# meteo_station_main.net
KiCad netlist of a schematic drawn in EasyEDA Pro
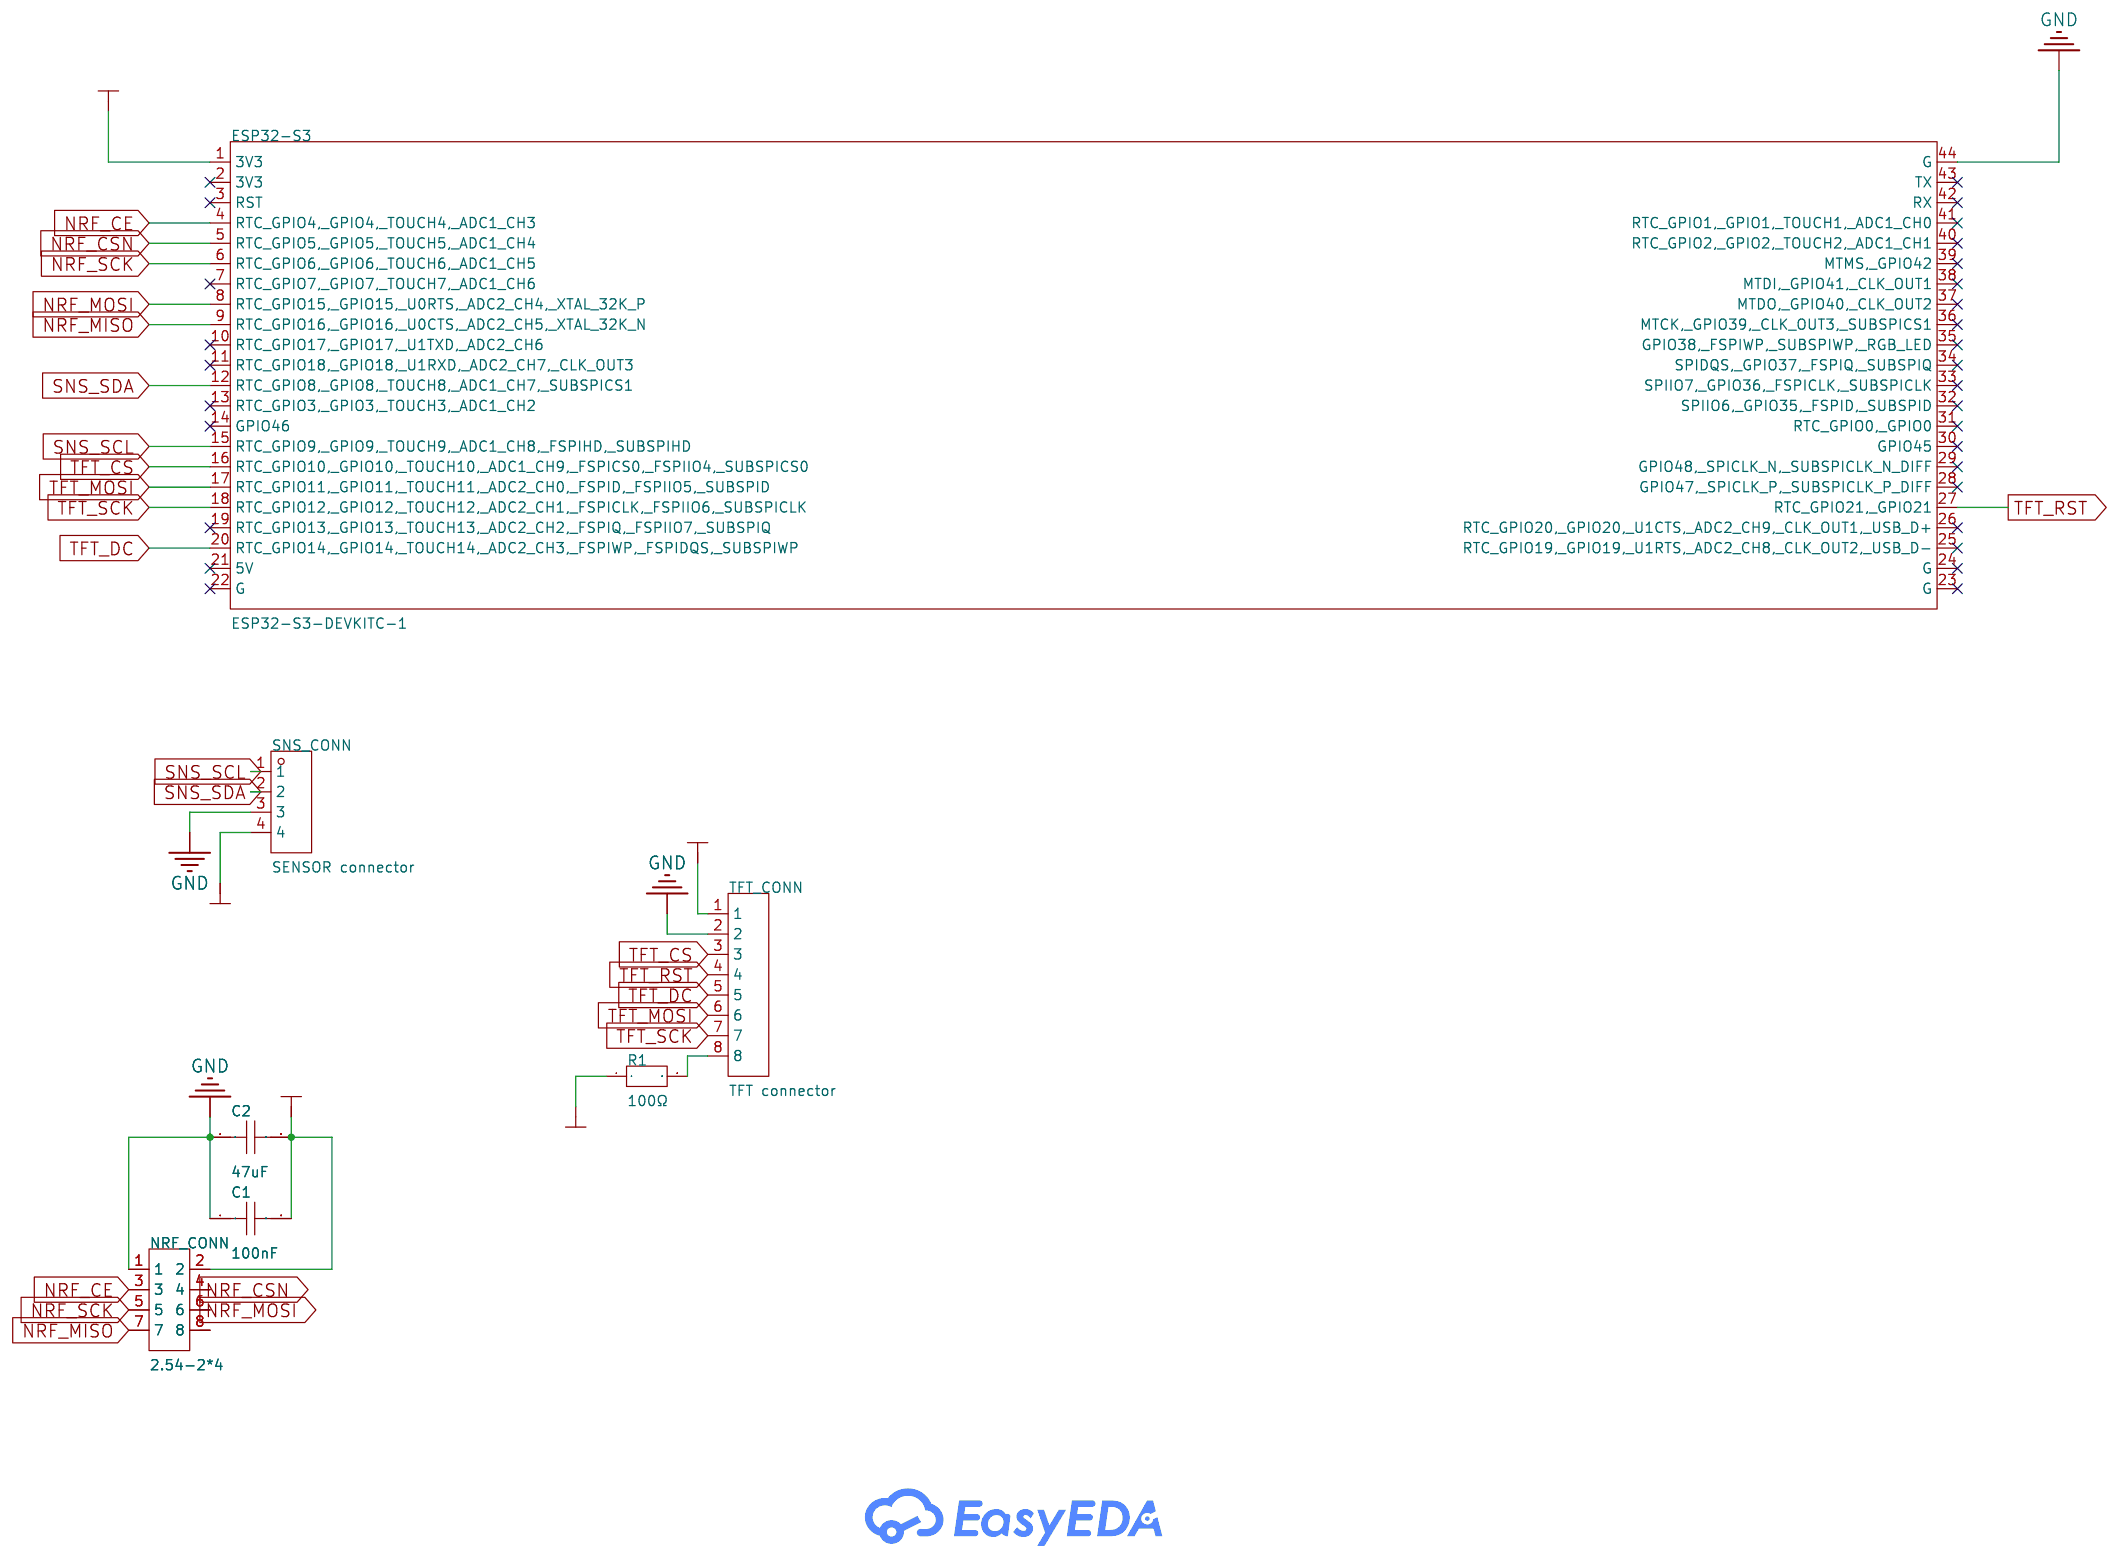
[diagram p0: schematic sheet]

(export (version "E")
  (design (tool "Eeschema 10.0.6"))
  (components
    (comp (ref "C1")
      (value "100nF")
      (footprint "easyedapro:CAP-TH_L5.5-W2.4-P5.08-D0.6")
      (fields
        (field (name "Manufacturer Part") "CC1H104ZC1ED3F5O1100")
        (field (name "Manufacturer") "Dersonic(德尔创)")
      )
      (libsource (lib "easyedapro") (part "CC1H104ZC1ED3F5O1100"))
    )
    (comp (ref "C2")
      (value "47uF")
      (footprint "easyedapro:CAP-TH_L5.5-W2.4-P5.08-D0.6")
      (fields
        (field (name "Manufacturer Part") "CC1H104ZC1ED3F5O1100")
        (field (name "Manufacturer") "Dersonic(德尔创)")
      )
      (libsource (lib "easyedapro") (part "CC1H104ZC1ED3F5O1100"))
    )
    (comp (ref "ESP32-S3")
      (value "ESP32-S3-DEVKITC-1")
      (footprint "easyedapro:CONN-TH_ESP32-S3-DEVKITC-1U-N8")
      (fields (field (name "Manufacturer") "ESPRESSIF(乐鑫)"))
      (libsource (lib "easyedapro") (part "ESP32-S3-DEVKITC-1-N8"))
    )
    (comp (ref "NRF_CONN")
      (value "2.54-2*4")
      (footprint "easyedapro:HDR-TH_8P-P2.54-V-F-R2-C4-S2.54")
      (fields (field (name "Manufacturer") "ZHOURI(洲日)"))
      (libsource (lib "easyedapro") (part "2.54-2*4"))
    )
    (comp (ref "R1")
      (value "100Ω")
      (footprint "easyedapro:RES-TH_BD5.6-L14.0-P18.00-D0.8")
      (description "Resistance: Tolerance:±1% Tolerance:±1%")
      (fields (field (name "Manufacturer Part") "RLP03100R0FB15") (field (name "Manufacturer") "VISHAY(威世)"))
      (libsource (lib "easyedapro") (part "RLP03100R0FB15"))
    )
    (comp (ref "SNS_CONN")
      (value "SENSOR connector")
      (footprint "easyedapro:HDR-TH_4P-P2.54-V-M-3")
      (libsource (lib "easyedapro") (part "SIP4-CON4排针"))
    )
    (comp (ref "TFT_CONN")
      (value "TFT connector")
      (footprint "easyedapro:CONN-TH_8P-P2.54_XH2.54_C9900012080")
      (libsource (lib "easyedapro") (part "XH2.54-8PIN"))
    )
  )
  (nets
    (net (code "1") (name "GND") (class "Default")
      (node (ref "C1") (pin "1") (pinfunction "1_1") (pintype "unspecified"))
      (node (ref "C2") (pin "1") (pinfunction "1_1") (pintype "unspecified"))
      (node (ref "ESP32-S3") (pin "44") (pinfunction "G_44") (pintype "unspecified"))
      (node (ref "NRF_CONN") (pin "1") (pinfunction "1_1") (pintype "unspecified"))
      (node (ref "SNS_CONN") (pin "3") (pinfunction "3_3") (pintype "unspecified"))
      (node (ref "TFT_CONN") (pin "2") (pinfunction "2_2") (pintype "unspecified"))
    )
    (net (code "2") (name "NRF_CE") (class "Default")
      (node (ref "ESP32-S3") (pin "4") (pinfunction "RTC_GPIO4,_GPIO4,_TOUCH4,_ADC1_CH3_4") (pintype "unspecified"))
      (node (ref "NRF_CONN") (pin "3") (pinfunction "3_3") (pintype "unspecified"))
    )
    (net (code "3") (name "NRF_CSN") (class "Default")
      (node (ref "ESP32-S3") (pin "5") (pinfunction "RTC_GPIO5,_GPIO5,_TOUCH5,_ADC1_CH4_5") (pintype "unspecified"))
      (node (ref "NRF_CONN") (pin "4") (pinfunction "4_4") (pintype "unspecified"))
    )
    (net (code "4") (name "NRF_MISO") (class "Default")
      (node (ref "ESP32-S3") (pin "9") (pinfunction "RTC_GPIO16,_GPIO16,_U0CTS,_ADC2_CH5,_XTAL_32K_N_9") (pintype "unspecified"))
      (node (ref "NRF_CONN") (pin "7") (pinfunction "7_7") (pintype "unspecified"))
    )
    (net (code "5") (name "NRF_MOSI") (class "Default")
      (node (ref "ESP32-S3") (pin "8") (pinfunction "RTC_GPIO15,_GPIO15,_U0RTS,_ADC2_CH4,_XTAL_32K_P_8") (pintype "unspecified"))
      (node (ref "NRF_CONN") (pin "6") (pinfunction "6_6") (pintype "unspecified"))
    )
    (net (code "6") (name "NRF_SCK") (class "Default")
      (node (ref "ESP32-S3") (pin "6") (pinfunction "RTC_GPIO6,_GPIO6,_TOUCH6,_ADC1_CH5_6") (pintype "unspecified"))
      (node (ref "NRF_CONN") (pin "5") (pinfunction "5_5") (pintype "unspecified"))
    )
    (net (code "7") (name "Net-(R1-Pad2)") (class "Default")
      (node (ref "R1") (pin "2") (pinfunction "2_2") (pintype "unspecified"))
      (node (ref "TFT_CONN") (pin "8") (pinfunction "8_8") (pintype "unspecified"))
    )
    (net (code "8") (name "SNS_SCL") (class "Default")
      (node (ref "ESP32-S3") (pin "15") (pinfunction "RTC_GPIO9,_GPIO9,_TOUCH9,_ADC1_CH8,_FSPIHD,_SUBSPIHD_15") (pintype "unspecified"))
      (node (ref "SNS_CONN") (pin "1") (pinfunction "1_1") (pintype "unspecified"))
    )
    (net (code "9") (name "SNS_SDA") (class "Default")
      (node (ref "ESP32-S3") (pin "12") (pinfunction "RTC_GPIO8,_GPIO8,_TOUCH8,_ADC1_CH7,_SUBSPICS1_12") (pintype "unspecified"))
      (node (ref "SNS_CONN") (pin "2") (pinfunction "2_2") (pintype "unspecified"))
    )
    (net (code "10") (name "TFT_CS") (class "Default")
      (node (ref "ESP32-S3") (pin "16") (pinfunction "RTC_GPIO10,_GPIO10,_TOUCH10,_ADC1_CH9,_FSPICS0,_FSPIIO4,_SUBSPICS0_16") (pintype "unspecified"))
      (node (ref "TFT_CONN") (pin "3") (pinfunction "3_3") (pintype "unspecified"))
    )
    (net (code "11") (name "TFT_DC") (class "Default")
      (node (ref "ESP32-S3") (pin "20") (pinfunction "RTC_GPIO14,_GPIO14,_TOUCH14,_ADC2_CH3,_FSPIWP,_FSPIDQS,_SUBSPIWP_20") (pintype "unspecified"))
      (node (ref "TFT_CONN") (pin "5") (pinfunction "5_5") (pintype "unspecified"))
    )
    (net (code "12") (name "TFT_MOSI") (class "Default")
      (node (ref "ESP32-S3") (pin "17") (pinfunction "RTC_GPIO11,_GPIO11,_TOUCH11,_ADC2_CH0,_FSPID,_FSPIIO5,_SUBSPID_17") (pintype "unspecified"))
      (node (ref "TFT_CONN") (pin "6") (pinfunction "6_6") (pintype "unspecified"))
    )
    (net (code "13") (name "TFT_RST") (class "Default")
      (node (ref "ESP32-S3") (pin "27") (pinfunction "RTC_GPIO21,_GPIO21_27") (pintype "unspecified"))
      (node (ref "TFT_CONN") (pin "4") (pinfunction "4_4") (pintype "unspecified"))
    )
    (net (code "14") (name "TFT_SCK") (class "Default")
      (node (ref "ESP32-S3") (pin "18") (pinfunction "RTC_GPIO12,_GPIO12,_TOUCH12,_ADC2_CH1,_FSPICLK,_FSPIIO6,_SUBSPICLK_18") (pintype "unspecified"))
      (node (ref "TFT_CONN") (pin "7") (pinfunction "7_7") (pintype "unspecified"))
    )
    (net (code "15") (name "VCC_3V3") (class "Default")
      (node (ref "C1") (pin "2") (pinfunction "2_2") (pintype "unspecified"))
      (node (ref "C2") (pin "2") (pinfunction "2_2") (pintype "unspecified"))
      (node (ref "ESP32-S3") (pin "1") (pinfunction "3V3_1") (pintype "unspecified"))
      (node (ref "NRF_CONN") (pin "2") (pinfunction "2_2") (pintype "unspecified"))
      (node (ref "R1") (pin "1") (pinfunction "1_1") (pintype "unspecified"))
      (node (ref "SNS_CONN") (pin "4") (pinfunction "4_4") (pintype "unspecified"))
      (node (ref "TFT_CONN") (pin "1") (pinfunction "1_1") (pintype "unspecified"))
    )
    (net (code "16") (name "unconnected-(ESP32-S3-3V3-Pad2)") (class "Default")
      (node (ref "ESP32-S3") (pin "2") (pinfunction "3V3_2") (pintype "unspecified+no_connect"))
    )
    (net (code "17") (name "unconnected-(ESP32-S3-5V-Pad21)") (class "Default")
      (node (ref "ESP32-S3") (pin "21") (pinfunction "5V_21") (pintype "unspecified+no_connect"))
    )
    (net (code "18") (name "unconnected-(ESP32-S3-G-Pad22)") (class "Default")
      (node (ref "ESP32-S3") (pin "22") (pinfunction "G_22") (pintype "unspecified+no_connect"))
    )
    (net (code "19") (name "unconnected-(ESP32-S3-G-Pad23)") (class "Default")
      (node (ref "ESP32-S3") (pin "23") (pinfunction "G_23") (pintype "unspecified+no_connect"))
    )
    (net (code "20") (name "unconnected-(ESP32-S3-G-Pad24)") (class "Default")
      (node (ref "ESP32-S3") (pin "24") (pinfunction "G_24") (pintype "unspecified+no_connect"))
    )
    (net (code "21") (name "unconnected-(ESP32-S3-GPIO38,_FSPIWP,_SUBSPIWP,_RGB_LED-Pad35)") (class "Default")
      (node (ref "ESP32-S3") (pin "35") (pinfunction "GPIO38,_FSPIWP,_SUBSPIWP,_RGB_LED_35") (pintype "unspecified+no_connect"))
    )
    (net (code "22") (name "unconnected-(ESP32-S3-GPIO45-Pad30)") (class "Default")
      (node (ref "ESP32-S3") (pin "30") (pinfunction "GPIO45_30") (pintype "unspecified+no_connect"))
    )
    (net (code "23") (name "unconnected-(ESP32-S3-GPIO46-Pad14)") (class "Default")
      (node (ref "ESP32-S3") (pin "14") (pinfunction "GPIO46_14") (pintype "unspecified+no_connect"))
    )
    (net (code "24") (name "unconnected-(ESP32-S3-GPIO47,_SPICLK_P,_SUBSPICLK_P_DIFF-Pad28)") (class "Default")
      (node (ref "ESP32-S3") (pin "28") (pinfunction "GPIO47,_SPICLK_P,_SUBSPICLK_P_DIFF_28") (pintype "unspecified+no_connect"))
    )
    (net (code "25") (name "unconnected-(ESP32-S3-GPIO48,_SPICLK_N,_SUBSPICLK_N_DIFF-Pad29)") (class "Default")
      (node (ref "ESP32-S3") (pin "29") (pinfunction "GPIO48,_SPICLK_N,_SUBSPICLK_N_DIFF_29") (pintype "unspecified+no_connect"))
    )
    (net (code "26") (name "unconnected-(ESP32-S3-MTCK,_GPIO39,_CLK_OUT3,_SUBSPICS1-Pad36)") (class "Default")
      (node (ref "ESP32-S3") (pin "36") (pinfunction "MTCK,_GPIO39,_CLK_OUT3,_SUBSPICS1_36") (pintype "unspecified+no_connect"))
    )
    (net (code "27") (name "unconnected-(ESP32-S3-MTDI,_GPIO41,_CLK_OUT1-Pad38)") (class "Default")
      (node (ref "ESP32-S3") (pin "38") (pinfunction "MTDI,_GPIO41,_CLK_OUT1_38") (pintype "unspecified+no_connect"))
    )
    (net (code "28") (name "unconnected-(ESP32-S3-MTDO,_GPIO40,_CLK_OUT2-Pad37)") (class "Default")
      (node (ref "ESP32-S3") (pin "37") (pinfunction "MTDO,_GPIO40,_CLK_OUT2_37") (pintype "unspecified+no_connect"))
    )
    (net (code "29") (name "unconnected-(ESP32-S3-MTMS,_GPIO42-Pad39)") (class "Default")
      (node (ref "ESP32-S3") (pin "39") (pinfunction "MTMS,_GPIO42_39") (pintype "unspecified+no_connect"))
    )
    (net (code "30") (name "unconnected-(ESP32-S3-RST-Pad3)") (class "Default")
      (node (ref "ESP32-S3") (pin "3") (pinfunction "RST_3") (pintype "unspecified+no_connect"))
    )
    (net (code "31") (name "unconnected-(ESP32-S3-RTC_GPIO0,_GPIO0-Pad31)") (class "Default")
      (node (ref "ESP32-S3") (pin "31") (pinfunction "RTC_GPIO0,_GPIO0_31") (pintype "unspecified+no_connect"))
    )
    (net (code "32") (name "unconnected-(ESP32-S3-RTC_GPIO1,_GPIO1,_TOUCH1,_ADC1_CH0-Pad41)") (class "Default")
      (node (ref "ESP32-S3") (pin "41") (pinfunction "RTC_GPIO1,_GPIO1,_TOUCH1,_ADC1_CH0_41") (pintype "unspecified+no_connect"))
    )
    (net (code "33") (name "unconnected-(ESP32-S3-RTC_GPIO2,_GPIO2,_TOUCH2,_ADC1_CH1-Pad40)") (class "Default")
      (node (ref "ESP32-S3") (pin "40") (pinfunction "RTC_GPIO2,_GPIO2,_TOUCH2,_ADC1_CH1_40") (pintype "unspecified+no_connect"))
    )
    (net (code "34") (name "unconnected-(ESP32-S3-RTC_GPIO3,_GPIO3,_TOUCH3,_ADC1_CH2-Pad13)") (class "Default")
      (node (ref "ESP32-S3") (pin "13") (pinfunction "RTC_GPIO3,_GPIO3,_TOUCH3,_ADC1_CH2_13") (pintype "unspecified+no_connect"))
    )
    (net (code "35") (name "unconnected-(ESP32-S3-RTC_GPIO7,_GPIO7,_TOUCH7,_ADC1_CH6-Pad7)") (class "Default")
      (node (ref "ESP32-S3") (pin "7") (pinfunction "RTC_GPIO7,_GPIO7,_TOUCH7,_ADC1_CH6_7") (pintype "unspecified+no_connect"))
    )
    (net (code "36") (name "unconnected-(ESP32-S3-RTC_GPIO13,_GPIO13,_TOUCH13,_ADC2_CH2,_FSPIQ,_FSPIIO7,_SUBSPIQ-Pad19)") (class "Default")
      (node (ref "ESP32-S3") (pin "19") (pinfunction "RTC_GPIO13,_GPIO13,_TOUCH13,_ADC2_CH2,_FSPIQ,_FSPIIO7,_SUBSPIQ_19") (pintype "unspecified+no_connect"))
    )
    (net (code "37") (name "unconnected-(ESP32-S3-RTC_GPIO17,_GPIO17,_U1TXD,_ADC2_CH6-Pad10)") (class "Default")
      (node (ref "ESP32-S3") (pin "10") (pinfunction "RTC_GPIO17,_GPIO17,_U1TXD,_ADC2_CH6_10") (pintype "unspecified+no_connect"))
    )
    (net (code "38") (name "unconnected-(ESP32-S3-RTC_GPIO18,_GPIO18,_U1RXD,_ADC2_CH7,_CLK_OUT3-Pad11)") (class "Default")
      (node (ref "ESP32-S3") (pin "11") (pinfunction "RTC_GPIO18,_GPIO18,_U1RXD,_ADC2_CH7,_CLK_OUT3_11") (pintype "unspecified+no_connect"))
    )
    (net (code "39") (name "unconnected-(ESP32-S3-RTC_GPIO19,_GPIO19,_U1RTS,_ADC2_CH8,_CLK_OUT2,_USB_D--Pad25)") (class "Default")
      (node (ref "ESP32-S3") (pin "25") (pinfunction "RTC_GPIO19,_GPIO19,_U1RTS,_ADC2_CH8,_CLK_OUT2,_USB_D-_25") (pintype "unspecified+no_connect"))
    )
    (net (code "40") (name "unconnected-(ESP32-S3-RTC_GPIO20,_GPIO20,_U1CTS,_ADC2_CH9,_CLK_OUT1,_USB_D+-Pad26)") (class "Default")
      (node (ref "ESP32-S3") (pin "26") (pinfunction "RTC_GPIO20,_GPIO20,_U1CTS,_ADC2_CH9,_CLK_OUT1,_USB_D+_26") (pintype "unspecified+no_connect"))
    )
    (net (code "41") (name "unconnected-(ESP32-S3-RX-Pad42)") (class "Default")
      (node (ref "ESP32-S3") (pin "42") (pinfunction "RX_42") (pintype "unspecified+no_connect"))
    )
    (net (code "42") (name "unconnected-(ESP32-S3-SPIDQS,_GPIO37,_FSPIQ,_SUBSPIQ-Pad34)") (class "Default")
      (node (ref "ESP32-S3") (pin "34") (pinfunction "SPIDQS,_GPIO37,_FSPIQ,_SUBSPIQ_34") (pintype "unspecified+no_connect"))
    )
    (net (code "43") (name "unconnected-(ESP32-S3-SPIIO6,_GPIO35,_FSPID,_SUBSPID-Pad32)") (class "Default")
      (node (ref "ESP32-S3") (pin "32") (pinfunction "SPIIO6,_GPIO35,_FSPID,_SUBSPID_32") (pintype "unspecified+no_connect"))
    )
    (net (code "44") (name "unconnected-(ESP32-S3-SPIIO7,_GPIO36,_FSPICLK,_SUBSPICLK-Pad33)") (class "Default")
      (node (ref "ESP32-S3") (pin "33") (pinfunction "SPIIO7,_GPIO36,_FSPICLK,_SUBSPICLK_33") (pintype "unspecified+no_connect"))
    )
    (net (code "45") (name "unconnected-(ESP32-S3-TX-Pad43)") (class "Default")
      (node (ref "ESP32-S3") (pin "43") (pinfunction "TX_43") (pintype "unspecified+no_connect"))
    )
    (net (code "46") (name "unconnected-(NRF_CONN-Pad8)") (class "Default")
      (node (ref "NRF_CONN") (pin "8") (pinfunction "8_8") (pintype "unspecified"))
    )
  )
)
